# SS_SECE_V2_0.net
KiCad netlist of a schematic drawn in Altium Designer
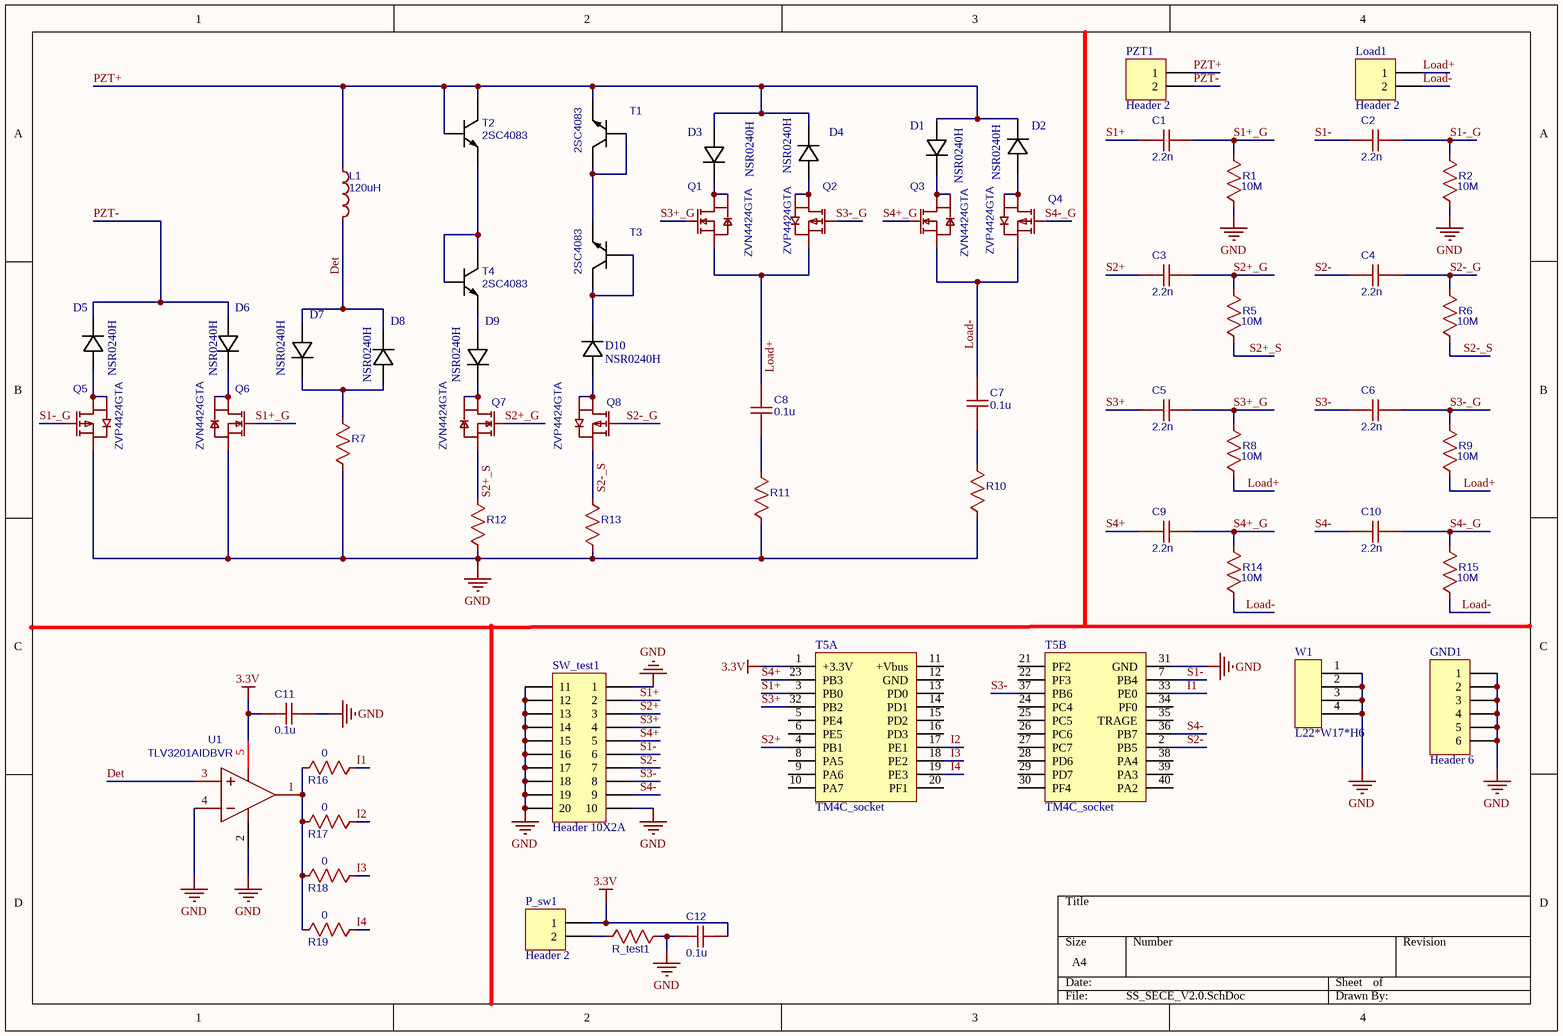
[diagram p0: SS_SECE_V2.0.SchDoc]

(export (version "E")
  (design (tool "Eeschema 10.0.6"))
  (components
    (comp (ref "C1")
      (value "2.2n")
      (footprint "C0603")
      (fields (field (name "CONTRIBUTOR") "LCEDA_Lib"))
      (libsource (lib "packet") (part "0.1u"))
    )
    (comp (ref "C2")
      (value "2.2n")
      (footprint "C0603")
      (fields (field (name "CONTRIBUTOR") "LCEDA_Lib"))
      (libsource (lib "packet") (part "0.1u"))
    )
    (comp (ref "C3")
      (value "2.2n")
      (footprint "C0603")
      (fields (field (name "CONTRIBUTOR") "LCEDA_Lib"))
      (libsource (lib "packet") (part "0.1u"))
    )
    (comp (ref "C4")
      (value "2.2n")
      (footprint "C0603")
      (fields (field (name "CONTRIBUTOR") "LCEDA_Lib"))
      (libsource (lib "packet") (part "0.1u"))
    )
    (comp (ref "C5")
      (value "2.2n")
      (footprint "C0603")
      (fields (field (name "CONTRIBUTOR") "LCEDA_Lib"))
      (libsource (lib "packet") (part "0.1u"))
    )
    (comp (ref "C6")
      (value "2.2n")
      (footprint "C0603")
      (fields (field (name "CONTRIBUTOR") "LCEDA_Lib"))
      (libsource (lib "packet") (part "0.1u"))
    )
    (comp (ref "C7")
      (value "0.1u")
      (footprint "Cap2220")
      (fields (field (name "CONTRIBUTOR") "LCEDA_Lib"))
      (libsource (lib "packet") (part "0.1u"))
    )
    (comp (ref "C8")
      (value "0.1u")
      (footprint "Cap2220")
      (fields (field (name "CONTRIBUTOR") "LCEDA_Lib"))
      (libsource (lib "packet") (part "0.1u"))
    )
    (comp (ref "C9")
      (value "2.2n")
      (footprint "C0603")
      (fields (field (name "CONTRIBUTOR") "LCEDA_Lib"))
      (libsource (lib "packet") (part "0.1u"))
    )
    (comp (ref "C10")
      (value "2.2n")
      (footprint "C0603")
      (fields (field (name "CONTRIBUTOR") "LCEDA_Lib"))
      (libsource (lib "packet") (part "0.1u"))
    )
    (comp (ref "C11")
      (value "0.1u")
      (footprint "C0603")
      (fields (field (name "CONTRIBUTOR") "LCEDA_Lib"))
      (libsource (lib "packet") (part "0.1u"))
    )
    (comp (ref "C12")
      (value "0.1u")
      (footprint "C0603")
      (fields (field (name "CONTRIBUTOR") "LCEDA_Lib"))
      (libsource (lib "packet") (part "0.1u"))
    )
    (comp (ref "D1") (value "NSR0240H") (footprint "SOD-323") (libsource (lib "packet") (part "NSR0240H")))
    (comp (ref "D2") (value "NSR0240H") (footprint "SOD-323") (libsource (lib "packet") (part "NSR0240H")))
    (comp (ref "D3") (value "NSR0240H") (footprint "SOD-323") (libsource (lib "packet") (part "NSR0240H")))
    (comp (ref "D4") (value "NSR0240H") (footprint "SOD-323") (libsource (lib "packet") (part "NSR0240H")))
    (comp (ref "D5") (value "NSR0240H") (footprint "SOD-323") (libsource (lib "packet") (part "NSR0240H")))
    (comp (ref "D6") (value "NSR0240H") (footprint "SOD-323") (libsource (lib "packet") (part "NSR0240H")))
    (comp (ref "D7") (value "NSR0240H") (footprint "SOD-323") (libsource (lib "packet") (part "NSR0240H")))
    (comp (ref "D8") (value "NSR0240H") (footprint "SOD-323") (libsource (lib "packet") (part "NSR0240H")))
    (comp (ref "D9") (value "NSR0240H") (footprint "SOD-323") (libsource (lib "packet") (part "NSR0240H")))
    (comp (ref "D10") (value "NSR0240H") (footprint "SOD-323") (libsource (lib "packet") (part "NSR0240H")))
    (comp (ref "GND1")
      (value "Header 6")
      (footprint "HDR1X6")
      (description "Header, 6-Pin")
      (fields (field (name "PUBLISHER") "Altium Limited"))
      (libsource (lib "Miscellaneous Connectors") (part "Header 6"))
    )
    (comp (ref "L1")
      (value "120uH")
      (footprint "120uH")
      (fields
        (field (name "BOM_MANUFACTURER PART") "VLU1012-470KB")
        (field (name "BOM_SUPPLIER PART") "C142466")
        (field (name "CONTRIBUTOR") "LCSC")
      )
      (libsource (lib "packet") (part "47uH"))
    )
    (comp (ref "Load1")
      (value "Header 2")
      (footprint "HDR1X2")
      (description "Header, 2-Pin")
      (fields (field (name "PUBLISHER") "Altium Limited"))
      (libsource (lib "Miscellaneous Connectors") (part "Header 2"))
    )
    (comp (ref "PZT1")
      (value "Header 2")
      (footprint "HDR1X2")
      (description "Header, 2-Pin")
      (fields (field (name "PUBLISHER") "Altium Limited"))
      (libsource (lib "Miscellaneous Connectors") (part "Header 2"))
    )
    (comp (ref "P_sw1")
      (value "Header 2")
      (footprint "HDR1X2")
      (description "Header, 2-Pin")
      (fields (field (name "PUBLISHER") "Altium Limited"))
      (libsource (lib "Miscellaneous Connectors") (part "Header 2"))
    )
    (comp (ref "Q1")
      (value "ZVN4424GTA")
      (footprint "SOT-223-4_L6.5-W3.5-P2.30-LS7.0-BR")
      (fields
        (field (name "BOM_SUPPLIER PART") "C397967")
        (field (name "BOM_MANUFACTURER PART") "ZVP4424GTA")
        (field (name "CONTRIBUTOR") "LCSC")
      )
      (libsource (lib "packet") (part "ZVN4424GTA"))
    )
    (comp (ref "Q2")
      (value "ZVP4424GTA")
      (footprint "SOT-223-4_L6.5-W3.5-P2.30-LS7.0-BR")
      (fields (field (name "BOM_SUPPLIER PART") "C397967") (field (name "CONTRIBUTOR") "LCSC"))
      (libsource (lib "packet") (part "ZVP4424GTA"))
    )
    (comp (ref "Q3")
      (value "ZVN4424GTA")
      (footprint "SOT-223-4_L6.5-W3.5-P2.30-LS7.0-BR")
      (fields
        (field (name "BOM_SUPPLIER PART") "C397967")
        (field (name "BOM_MANUFACTURER PART") "ZVP4424GTA")
        (field (name "CONTRIBUTOR") "LCSC")
      )
      (libsource (lib "packet") (part "ZVN4424GTA"))
    )
    (comp (ref "Q4")
      (value "ZVP4424GTA")
      (footprint "SOT-223-4_L6.5-W3.5-P2.30-LS7.0-BR")
      (fields (field (name "BOM_SUPPLIER PART") "C397967") (field (name "CONTRIBUTOR") "LCSC"))
      (libsource (lib "packet") (part "ZVP4424GTA"))
    )
    (comp (ref "Q5")
      (value "ZVP4424GTA")
      (footprint "SOT-223-4_L6.5-W3.5-P2.30-LS7.0-BR")
      (fields (field (name "BOM_SUPPLIER PART") "C397967") (field (name "CONTRIBUTOR") "LCSC"))
      (libsource (lib "packet") (part "ZVP4424GTA"))
    )
    (comp (ref "Q6")
      (value "ZVN4424GTA")
      (footprint "SOT-223-4_L6.5-W3.5-P2.30-LS7.0-BR")
      (fields
        (field (name "BOM_SUPPLIER PART") "C397967")
        (field (name "BOM_MANUFACTURER PART") "ZVP4424GTA")
        (field (name "CONTRIBUTOR") "LCSC")
      )
      (libsource (lib "packet") (part "ZVN4424GTA"))
    )
    (comp (ref "Q7")
      (value "ZVN4424GTA")
      (footprint "SOT-223-4_L6.5-W3.5-P2.30-LS7.0-BR")
      (fields
        (field (name "BOM_SUPPLIER PART") "C397967")
        (field (name "BOM_MANUFACTURER PART") "ZVP4424GTA")
        (field (name "CONTRIBUTOR") "LCSC")
      )
      (libsource (lib "packet") (part "ZVN4424GTA"))
    )
    (comp (ref "Q8")
      (value "ZVP4424GTA")
      (footprint "SOT-223-4_L6.5-W3.5-P2.30-LS7.0-BR")
      (fields (field (name "BOM_SUPPLIER PART") "C397967") (field (name "CONTRIBUTOR") "LCSC"))
      (libsource (lib "packet") (part "ZVP4424GTA"))
    )
    (comp (ref "R1")
      (value "10M")
      (footprint "R0603")
      (fields (field (name "CONTRIBUTOR") "LCEDA_Lib"))
      (libsource (lib "packet") (part "1k"))
    )
    (comp (ref "R2")
      (value "10M")
      (footprint "R0603")
      (fields (field (name "CONTRIBUTOR") "LCEDA_Lib"))
      (libsource (lib "packet") (part "1k"))
    )
    (comp (ref "R5")
      (value "10M")
      (footprint "R0603")
      (fields (field (name "CONTRIBUTOR") "LCEDA_Lib"))
      (libsource (lib "packet") (part "1k"))
    )
    (comp (ref "R6")
      (value "10M")
      (footprint "R0603")
      (fields (field (name "CONTRIBUTOR") "LCEDA_Lib"))
      (libsource (lib "packet") (part "1k"))
    )
    (comp (ref "R7")
      (value "0")
      (footprint "R0603")
      (fields (field (name "CONTRIBUTOR") "LCEDA_Lib"))
      (libsource (lib "packet") (part "1k"))
    )
    (comp (ref "R8")
      (value "10M")
      (footprint "R0603")
      (fields (field (name "CONTRIBUTOR") "LCEDA_Lib"))
      (libsource (lib "packet") (part "1k"))
    )
    (comp (ref "R9")
      (value "10M")
      (footprint "R0603")
      (fields (field (name "CONTRIBUTOR") "LCEDA_Lib"))
      (libsource (lib "packet") (part "1k"))
    )
    (comp (ref "R10")
      (value "0")
      (footprint "R0603")
      (fields (field (name "CONTRIBUTOR") "LCEDA_Lib"))
      (libsource (lib "packet") (part "1k"))
    )
    (comp (ref "R11")
      (value "0")
      (footprint "R0603")
      (fields (field (name "CONTRIBUTOR") "LCEDA_Lib"))
      (libsource (lib "packet") (part "1k"))
    )
    (comp (ref "R12")
      (value "0")
      (footprint "R0603")
      (fields (field (name "CONTRIBUTOR") "LCEDA_Lib"))
      (libsource (lib "packet") (part "1k"))
    )
    (comp (ref "R13")
      (value "0")
      (footprint "R0603")
      (fields (field (name "CONTRIBUTOR") "LCEDA_Lib"))
      (libsource (lib "packet") (part "1k"))
    )
    (comp (ref "R14")
      (value "10M")
      (footprint "R0603")
      (fields (field (name "CONTRIBUTOR") "LCEDA_Lib"))
      (libsource (lib "packet") (part "1k"))
    )
    (comp (ref "R15")
      (value "10M")
      (footprint "R0603")
      (fields (field (name "CONTRIBUTOR") "LCEDA_Lib"))
      (libsource (lib "packet") (part "1k"))
    )
    (comp (ref "R16")
      (value "0")
      (footprint "R0603")
      (fields (field (name "CONTRIBUTOR") "LCEDA_Lib"))
      (libsource (lib "packet") (part "1k"))
    )
    (comp (ref "R17")
      (value "0")
      (footprint "R0603")
      (fields (field (name "CONTRIBUTOR") "LCEDA_Lib"))
      (libsource (lib "packet") (part "1k"))
    )
    (comp (ref "R18")
      (value "0")
      (footprint "R0603")
      (fields (field (name "CONTRIBUTOR") "LCEDA_Lib"))
      (libsource (lib "packet") (part "1k"))
    )
    (comp (ref "R19")
      (value "0")
      (footprint "R0603")
      (fields (field (name "CONTRIBUTOR") "LCEDA_Lib"))
      (libsource (lib "packet") (part "1k"))
    )
    (comp (ref "R_test1")
      (value "1k")
      (footprint "R0603")
      (fields (field (name "CONTRIBUTOR") "LCEDA_Lib"))
      (libsource (lib "packet") (part "1k"))
    )
    (comp (ref "SW_test1")
      (value "Header 10X2A")
      (footprint "HDR2X10_CEN")
      (description "Header, 10-Pin, Dual row")
      (fields (field (name "PUBLISHER") "Altium Limited"))
      (libsource (lib "Miscellaneous Connectors") (part "Header 10X2A"))
    )
    (comp (ref "T1") (value "2SC4083") (footprint "SOT 323") (libsource (lib "packet") (part "2SC4083")))
    (comp (ref "T2") (value "2SC4083") (footprint "SOT 323") (libsource (lib "packet") (part "2SC4083")))
    (comp (ref "T3") (value "2SC4083") (footprint "SOT 323") (libsource (lib "packet") (part "2SC4083")))
    (comp (ref "T4") (value "2SC4083") (footprint "SOT 323") (libsource (lib "packet") (part "2SC4083")))
    (comp (ref "T5")
      (value "TM4C_socket")
      (footprint "Tm4c_socket")
      (libsource (lib "") (part "Tm4c_socket_1"))
    )
    (comp (ref "U1")
      (value "TLV3201AIDBVR")
      (footprint "SOT-23-5_L3.0-W1.7-P0.95-LS2.8-BR")
      (fields (field (name "BOM_SUPPLIER PART") "C105188"))
      (libsource (lib "packet") (part "TLV3201AIDBVR"))
    )
    (comp (ref "W1")
      (value "L22*W17*H6")
      (footprint "L22*W17*H6")
      (libsource (lib "packet") (part "L22*W17*H6"))
    )
  )
  (nets
    (net (code "1") (name "/Det") (class "Default")
      (node (ref "D7") (pin "2") (pinfunction "A_2") (pintype "passive"))
      (node (ref "D8") (pin "1") (pinfunction "C_1") (pintype "passive"))
      (node (ref "L1") (pin "2") (pinfunction "2_2") (pintype "passive"))
      (node (ref "U1") (pin "3") (pinfunction "IN+_3") (pintype "passive"))
    )
    (net (code "2") (name "/I1") (class "Default")
      (node (ref "R16") (pin "2") (pinfunction "2_2") (pintype "passive"))
      (node (ref "T5") (pin "33") (pinfunction "PE0_33") (pintype "passive"))
    )
    (net (code "3") (name "/I2") (class "Default")
      (node (ref "R17") (pin "2") (pinfunction "2_2") (pintype "passive"))
      (node (ref "T5") (pin "17") (pinfunction "PE1_17") (pintype "passive"))
    )
    (net (code "4") (name "/I3") (class "Default")
      (node (ref "R18") (pin "2") (pinfunction "2_2") (pintype "passive"))
      (node (ref "T5") (pin "18") (pinfunction "PE2_18") (pintype "passive"))
    )
    (net (code "5") (name "/I4") (class "Default")
      (node (ref "R19") (pin "2") (pinfunction "2_2") (pintype "passive"))
      (node (ref "T5") (pin "19") (pinfunction "PE3_19") (pintype "passive"))
    )
    (net (code "6") (name "/Load+") (class "Default")
      (node (ref "C8") (pin "2") (pinfunction "2_2") (pintype "passive"))
      (node (ref "Load1") (pin "1") (pinfunction "1_1") (pintype "passive"))
      (node (ref "Q1") (pin "3") (pinfunction "S_3") (pintype "passive"))
      (node (ref "Q2") (pin "3") (pinfunction "S_3") (pintype "passive"))
      (node (ref "R8") (pin "1") (pinfunction "1_1") (pintype "passive"))
      (node (ref "R9") (pin "1") (pinfunction "1_1") (pintype "passive"))
    )
    (net (code "7") (name "/Load-") (class "Default")
      (node (ref "C7") (pin "2") (pinfunction "2_2") (pintype "passive"))
      (node (ref "Load1") (pin "2") (pinfunction "2_2") (pintype "passive"))
      (node (ref "Q3") (pin "3") (pinfunction "S_3") (pintype "passive"))
      (node (ref "Q4") (pin "3") (pinfunction "S_3") (pintype "passive"))
      (node (ref "R14") (pin "1") (pinfunction "1_1") (pintype "passive"))
      (node (ref "R15") (pin "1") (pinfunction "1_1") (pintype "passive"))
    )
    (net (code "8") (name "/PZT+") (class "Default")
      (node (ref "D1") (pin "2") (pinfunction "A_2") (pintype "passive"))
      (node (ref "D2") (pin "1") (pinfunction "C_1") (pintype "passive"))
      (node (ref "D3") (pin "2") (pinfunction "A_2") (pintype "passive"))
      (node (ref "D4") (pin "1") (pinfunction "C_1") (pintype "passive"))
      (node (ref "L1") (pin "1") (pinfunction "1_1") (pintype "passive"))
      (node (ref "PZT1") (pin "1") (pinfunction "1_1") (pintype "passive"))
      (node (ref "T1") (pin "1") (pinfunction "E_1") (pintype "passive"))
      (node (ref "T2") (pin "2") (pinfunction "B_2") (pintype "passive"))
      (node (ref "T2") (pin "3") (pinfunction "C_3") (pintype "passive"))
    )
    (net (code "9") (name "/PZT-") (class "Default")
      (node (ref "D5") (pin "1") (pinfunction "C_1") (pintype "passive"))
      (node (ref "D6") (pin "2") (pinfunction "A_2") (pintype "passive"))
      (node (ref "PZT1") (pin "2") (pinfunction "2_2") (pintype "passive"))
    )
    (net (code "10") (name "/S1+") (class "Default")
      (node (ref "C1") (pin "1") (pinfunction "1_1") (pintype "passive"))
      (node (ref "SW_test1") (pin "2") (pinfunction "2_2") (pintype "passive"))
      (node (ref "T5") (pin "3") (pinfunction "PB0_3") (pintype "passive"))
    )
    (net (code "11") (name "/S1+_G") (class "Default")
      (node (ref "C1") (pin "2") (pinfunction "2_2") (pintype "passive"))
      (node (ref "Q6") (pin "1") (pinfunction "G_1") (pintype "passive"))
      (node (ref "R1") (pin "2") (pinfunction "2_2") (pintype "passive"))
    )
    (net (code "12") (name "/S1-") (class "Default")
      (node (ref "C2") (pin "1") (pinfunction "1_1") (pintype "passive"))
      (node (ref "SW_test1") (pin "6") (pinfunction "6_6") (pintype "passive"))
      (node (ref "T5") (pin "7") (pinfunction "PB4_7") (pintype "passive"))
    )
    (net (code "13") (name "/S1-_G") (class "Default")
      (node (ref "C2") (pin "2") (pinfunction "2_2") (pintype "passive"))
      (node (ref "Q5") (pin "1") (pinfunction "G_1") (pintype "passive"))
      (node (ref "R2") (pin "2") (pinfunction "2_2") (pintype "passive"))
    )
    (net (code "14") (name "/S2+") (class "Default")
      (node (ref "C3") (pin "1") (pinfunction "1_1") (pintype "passive"))
      (node (ref "SW_test1") (pin "3") (pinfunction "3_3") (pintype "passive"))
      (node (ref "T5") (pin "4") (pinfunction "PB1_4") (pintype "passive"))
    )
    (net (code "15") (name "/S2+_G") (class "Default")
      (node (ref "C3") (pin "2") (pinfunction "2_2") (pintype "passive"))
      (node (ref "Q7") (pin "1") (pinfunction "G_1") (pintype "passive"))
      (node (ref "R5") (pin "2") (pinfunction "2_2") (pintype "passive"))
    )
    (net (code "16") (name "/S2+_S") (class "Default")
      (node (ref "Q7") (pin "3") (pinfunction "S_3") (pintype "passive"))
      (node (ref "R12") (pin "2") (pinfunction "2_2") (pintype "passive"))
      (node (ref "R5") (pin "1") (pinfunction "1_1") (pintype "passive"))
    )
    (net (code "17") (name "/S2-") (class "Default")
      (node (ref "C4") (pin "1") (pinfunction "1_1") (pintype "passive"))
      (node (ref "SW_test1") (pin "7") (pinfunction "7_7") (pintype "passive"))
      (node (ref "T5") (pin "2") (pinfunction "PB5_2") (pintype "passive"))
    )
    (net (code "18") (name "/S2-_G") (class "Default")
      (node (ref "C4") (pin "2") (pinfunction "2_2") (pintype "passive"))
      (node (ref "Q8") (pin "1") (pinfunction "G_1") (pintype "passive"))
      (node (ref "R6") (pin "2") (pinfunction "2_2") (pintype "passive"))
    )
    (net (code "19") (name "/S2-_S") (class "Default")
      (node (ref "Q8") (pin "3") (pinfunction "S_3") (pintype "passive"))
      (node (ref "R13") (pin "2") (pinfunction "2_2") (pintype "passive"))
      (node (ref "R6") (pin "1") (pinfunction "1_1") (pintype "passive"))
    )
    (net (code "20") (name "/S3+") (class "Default")
      (node (ref "C5") (pin "1") (pinfunction "1_1") (pintype "passive"))
      (node (ref "SW_test1") (pin "4") (pinfunction "4_4") (pintype "passive"))
      (node (ref "T5") (pin "32") (pinfunction "PB2_32") (pintype "passive"))
    )
    (net (code "21") (name "/S3+_G") (class "Default")
      (node (ref "C5") (pin "2") (pinfunction "2_2") (pintype "passive"))
      (node (ref "Q1") (pin "1") (pinfunction "G_1") (pintype "passive"))
      (node (ref "R8") (pin "2") (pinfunction "2_2") (pintype "passive"))
    )
    (net (code "22") (name "/S3-") (class "Default")
      (node (ref "C6") (pin "1") (pinfunction "1_1") (pintype "passive"))
      (node (ref "SW_test1") (pin "8") (pinfunction "8_8") (pintype "passive"))
      (node (ref "T5") (pin "37") (pinfunction "PB6_37") (pintype "passive"))
    )
    (net (code "23") (name "/S3-_G") (class "Default")
      (node (ref "C6") (pin "2") (pinfunction "2_2") (pintype "passive"))
      (node (ref "Q2") (pin "1") (pinfunction "G_1") (pintype "passive"))
      (node (ref "R9") (pin "2") (pinfunction "2_2") (pintype "passive"))
    )
    (net (code "24") (name "/S4+") (class "Default")
      (node (ref "C9") (pin "1") (pinfunction "1_1") (pintype "passive"))
      (node (ref "SW_test1") (pin "5") (pinfunction "5_5") (pintype "passive"))
      (node (ref "T5") (pin "23") (pinfunction "PB3_23") (pintype "passive"))
    )
    (net (code "25") (name "/S4+_G") (class "Default")
      (node (ref "C9") (pin "2") (pinfunction "2_2") (pintype "passive"))
      (node (ref "Q3") (pin "1") (pinfunction "G_1") (pintype "passive"))
      (node (ref "R14") (pin "2") (pinfunction "2_2") (pintype "passive"))
    )
    (net (code "26") (name "/S4-") (class "Default")
      (node (ref "C10") (pin "1") (pinfunction "1_1") (pintype "passive"))
      (node (ref "SW_test1") (pin "9") (pinfunction "9_9") (pintype "passive"))
      (node (ref "T5") (pin "36") (pinfunction "PB7_36") (pintype "passive"))
    )
    (net (code "27") (name "/S4-_G") (class "Default")
      (node (ref "C10") (pin "2") (pinfunction "2_2") (pintype "passive"))
      (node (ref "Q4") (pin "1") (pinfunction "G_1") (pintype "passive"))
      (node (ref "R15") (pin "2") (pinfunction "2_2") (pintype "passive"))
    )
    (net (code "28") (name "3.3V") (class "Default")
      (node (ref "C11") (pin "1") (pinfunction "1_1") (pintype "passive"))
      (node (ref "C12") (pin "1") (pinfunction "1_1") (pintype "passive"))
      (node (ref "P_sw1") (pin "1") (pinfunction "1_1") (pintype "passive"))
      (node (ref "T5") (pin "1") (pinfunction "+3.3V_1") (pintype "passive"))
      (node (ref "U1") (pin "5") (pinfunction "VCC_5") (pintype "passive"))
    )
    (net (code "29") (name "GND") (class "Default")
      (node (ref "C11") (pin "2") (pinfunction "2_2") (pintype "passive"))
      (node (ref "C12") (pin "2") (pinfunction "2_2") (pintype "passive"))
      (node (ref "GND1") (pin "1") (pinfunction "1_1") (pintype "passive"))
      (node (ref "GND1") (pin "2") (pinfunction "2_2") (pintype "passive"))
      (node (ref "GND1") (pin "3") (pinfunction "3_3") (pintype "passive"))
      (node (ref "GND1") (pin "4") (pinfunction "4_4") (pintype "passive"))
      (node (ref "GND1") (pin "5") (pinfunction "5_5") (pintype "passive"))
      (node (ref "GND1") (pin "6") (pinfunction "6_6") (pintype "passive"))
      (node (ref "Q5") (pin "3") (pinfunction "S_3") (pintype "passive"))
      (node (ref "Q6") (pin "3") (pinfunction "S_3") (pintype "passive"))
      (node (ref "R1") (pin "1") (pinfunction "1_1") (pintype "passive"))
      (node (ref "R10") (pin "1") (pinfunction "1_1") (pintype "passive"))
      (node (ref "R11") (pin "1") (pinfunction "1_1") (pintype "passive"))
      (node (ref "R12") (pin "1") (pinfunction "1_1") (pintype "passive"))
      (node (ref "R13") (pin "1") (pinfunction "1_1") (pintype "passive"))
      (node (ref "R2") (pin "1") (pinfunction "1_1") (pintype "passive"))
      (node (ref "R7") (pin "1") (pinfunction "1_1") (pintype "passive"))
      (node (ref "R_test1") (pin "2") (pinfunction "2_2") (pintype "passive"))
      (node (ref "SW_test1") (pin "1") (pinfunction "1_1") (pintype "passive"))
      (node (ref "SW_test1") (pin "10") (pinfunction "10_10") (pintype "passive"))
      (node (ref "SW_test1") (pin "11") (pinfunction "11_11") (pintype "passive"))
      (node (ref "SW_test1") (pin "12") (pinfunction "12_12") (pintype "passive"))
      (node (ref "SW_test1") (pin "13") (pinfunction "13_13") (pintype "passive"))
      (node (ref "SW_test1") (pin "14") (pinfunction "14_14") (pintype "passive"))
      (node (ref "SW_test1") (pin "15") (pinfunction "15_15") (pintype "passive"))
      (node (ref "SW_test1") (pin "16") (pinfunction "16_16") (pintype "passive"))
      (node (ref "SW_test1") (pin "17") (pinfunction "17_17") (pintype "passive"))
      (node (ref "SW_test1") (pin "18") (pinfunction "18_18") (pintype "passive"))
      (node (ref "SW_test1") (pin "19") (pinfunction "19_19") (pintype "passive"))
      (node (ref "SW_test1") (pin "20") (pinfunction "20_20") (pintype "passive"))
      (node (ref "T5") (pin "31") (pinfunction "GND_31") (pintype "passive"))
      (node (ref "U1") (pin "2") (pinfunction "GND_2") (pintype "passive"))
      (node (ref "U1") (pin "4") (pinfunction "IN-_4") (pintype "passive"))
      (node (ref "W1") (pin "1") (pinfunction "GND_1") (pintype "passive"))
      (node (ref "W1") (pin "2") (pinfunction "2_2") (pintype "passive"))
      (node (ref "W1") (pin "3") (pinfunction "3_3") (pintype "passive"))
      (node (ref "W1") (pin "4") (pinfunction "4_4") (pintype "passive"))
    )
    (net (code "30") (name "Net-(C7-Pad1)") (class "Default")
      (node (ref "C7") (pin "1") (pinfunction "1_1") (pintype "passive"))
      (node (ref "R10") (pin "2") (pinfunction "2_2") (pintype "passive"))
    )
    (net (code "31") (name "Net-(C8-Pad1)") (class "Default")
      (node (ref "C8") (pin "1") (pinfunction "1_1") (pintype "passive"))
      (node (ref "R11") (pin "2") (pinfunction "2_2") (pintype "passive"))
    )
    (net (code "32") (name "Net-(D1-C)") (class "Default")
      (node (ref "D1") (pin "1") (pinfunction "C_1") (pintype "passive"))
      (node (ref "Q3") (pin "2") (pinfunction "D_2") (pintype "passive"))
      (node (ref "Q3") (pin "4") (pinfunction "D_4") (pintype "passive"))
    )
    (net (code "33") (name "Net-(D2-A)") (class "Default")
      (node (ref "D2") (pin "2") (pinfunction "A_2") (pintype "passive"))
      (node (ref "Q4") (pin "2") (pinfunction "D_2") (pintype "passive"))
      (node (ref "Q4") (pin "4") (pinfunction "D_4") (pintype "passive"))
    )
    (net (code "34") (name "Net-(D3-C)") (class "Default")
      (node (ref "D3") (pin "1") (pinfunction "C_1") (pintype "passive"))
      (node (ref "Q1") (pin "2") (pinfunction "D_2") (pintype "passive"))
      (node (ref "Q1") (pin "4") (pinfunction "D_4") (pintype "passive"))
    )
    (net (code "35") (name "Net-(D4-A)") (class "Default")
      (node (ref "D4") (pin "2") (pinfunction "A_2") (pintype "passive"))
      (node (ref "Q2") (pin "2") (pinfunction "D_2") (pintype "passive"))
      (node (ref "Q2") (pin "4") (pinfunction "D_4") (pintype "passive"))
    )
    (net (code "36") (name "Net-(D5-A)") (class "Default")
      (node (ref "D5") (pin "2") (pinfunction "A_2") (pintype "passive"))
      (node (ref "Q5") (pin "2") (pinfunction "D_2") (pintype "passive"))
      (node (ref "Q5") (pin "4") (pinfunction "D_4") (pintype "passive"))
    )
    (net (code "37") (name "Net-(D6-C)") (class "Default")
      (node (ref "D6") (pin "1") (pinfunction "C_1") (pintype "passive"))
      (node (ref "Q6") (pin "2") (pinfunction "D_2") (pintype "passive"))
      (node (ref "Q6") (pin "4") (pinfunction "D_4") (pintype "passive"))
    )
    (net (code "38") (name "Net-(D7-C)") (class "Default")
      (node (ref "D7") (pin "1") (pinfunction "C_1") (pintype "passive"))
      (node (ref "D8") (pin "2") (pinfunction "A_2") (pintype "passive"))
      (node (ref "R7") (pin "2") (pinfunction "2_2") (pintype "passive"))
    )
    (net (code "39") (name "Net-(D9-A)") (class "Default")
      (node (ref "D9") (pin "2") (pinfunction "A_2") (pintype "passive"))
      (node (ref "T4") (pin "1") (pinfunction "E_1") (pintype "passive"))
    )
    (net (code "40") (name "Net-(D9-C)") (class "Default")
      (node (ref "D9") (pin "1") (pinfunction "C_1") (pintype "passive"))
      (node (ref "Q7") (pin "2") (pinfunction "D_2") (pintype "passive"))
      (node (ref "Q7") (pin "4") (pinfunction "D_4") (pintype "passive"))
    )
    (net (code "41") (name "Net-(D10-A)") (class "Default")
      (node (ref "D10") (pin "2") (pinfunction "A_2") (pintype "passive"))
      (node (ref "Q8") (pin "2") (pinfunction "D_2") (pintype "passive"))
      (node (ref "Q8") (pin "4") (pinfunction "D_4") (pintype "passive"))
    )
    (net (code "42") (name "Net-(D10-C)") (class "Default")
      (node (ref "D10") (pin "1") (pinfunction "C_1") (pintype "passive"))
      (node (ref "T3") (pin "2") (pinfunction "B_2") (pintype "passive"))
      (node (ref "T3") (pin "3") (pinfunction "C_3") (pintype "passive"))
    )
    (net (code "43") (name "Net-(P_sw1-Pad2)") (class "Default")
      (node (ref "P_sw1") (pin "2") (pinfunction "2_2") (pintype "passive"))
      (node (ref "R_test1") (pin "1") (pinfunction "1_1") (pintype "passive"))
    )
    (net (code "44") (name "Net-(T1-B)") (class "Default")
      (node (ref "T1") (pin "2") (pinfunction "B_2") (pintype "passive"))
      (node (ref "T1") (pin "3") (pinfunction "C_3") (pintype "passive"))
      (node (ref "T3") (pin "1") (pinfunction "E_1") (pintype "passive"))
    )
    (net (code "45") (name "Net-(T2-E)") (class "Default")
      (node (ref "T2") (pin "1") (pinfunction "E_1") (pintype "passive"))
      (node (ref "T4") (pin "2") (pinfunction "B_2") (pintype "passive"))
      (node (ref "T4") (pin "3") (pinfunction "C_3") (pintype "passive"))
    )
    (net (code "46") (name "Net-(U1-OUT)") (class "Default")
      (node (ref "R16") (pin "1") (pinfunction "1_1") (pintype "passive"))
      (node (ref "R17") (pin "1") (pinfunction "1_1") (pintype "passive"))
      (node (ref "R18") (pin "1") (pinfunction "1_1") (pintype "passive"))
      (node (ref "R19") (pin "1") (pinfunction "1_1") (pintype "passive"))
      (node (ref "U1") (pin "1") (pinfunction "OUT_1") (pintype "passive"))
    )
    (net (code "47") (name "unconnected-(T5A-+Vbus-Pad11)") (class "Default")
      (node (ref "T5") (pin "11") (pinfunction "+Vbus_11") (pintype "passive"))
    )
    (net (code "48") (name "unconnected-(T5A-GND-Pad12)") (class "Default")
      (node (ref "T5") (pin "12") (pinfunction "GND_12") (pintype "passive"))
    )
    (net (code "49") (name "unconnected-(T5A-PA5-Pad8)") (class "Default")
      (node (ref "T5") (pin "8") (pinfunction "PA5_8") (pintype "passive"))
    )
    (net (code "50") (name "unconnected-(T5A-PA6-Pad9)") (class "Default")
      (node (ref "T5") (pin "9") (pinfunction "PA6_9") (pintype "passive"))
    )
    (net (code "51") (name "unconnected-(T5A-PA7-Pad10)") (class "Default")
      (node (ref "T5") (pin "10") (pinfunction "PA7_10") (pintype "passive"))
    )
    (net (code "52") (name "unconnected-(T5A-PD0-Pad13)") (class "Default")
      (node (ref "T5") (pin "13") (pinfunction "PD0_13") (pintype "passive"))
    )
    (net (code "53") (name "unconnected-(T5A-PD1-Pad14)") (class "Default")
      (node (ref "T5") (pin "14") (pinfunction "PD1_14") (pintype "passive"))
    )
    (net (code "54") (name "unconnected-(T5A-PD2-Pad15)") (class "Default")
      (node (ref "T5") (pin "15") (pinfunction "PD2_15") (pintype "passive"))
    )
    (net (code "55") (name "unconnected-(T5A-PD3-Pad16)") (class "Default")
      (node (ref "T5") (pin "16") (pinfunction "PD3_16") (pintype "passive"))
    )
    (net (code "56") (name "unconnected-(T5A-PE4-Pad5)") (class "Default")
      (node (ref "T5") (pin "5") (pinfunction "PE4_5") (pintype "passive"))
    )
    (net (code "57") (name "unconnected-(T5A-PE5-Pad6)") (class "Default")
      (node (ref "T5") (pin "6") (pinfunction "PE5_6") (pintype "passive"))
    )
    (net (code "58") (name "unconnected-(T5A-PF1-Pad20)") (class "Default")
      (node (ref "T5") (pin "20") (pinfunction "PF1_20") (pintype "passive"))
    )
    (net (code "59") (name "unconnected-(T5B-PA2-Pad40)") (class "Default")
      (node (ref "T5") (pin "40") (pinfunction "PA2_40") (pintype "passive"))
    )
    (net (code "60") (name "unconnected-(T5B-PA3-Pad39)") (class "Default")
      (node (ref "T5") (pin "39") (pinfunction "PA3_39") (pintype "passive"))
    )
    (net (code "61") (name "unconnected-(T5B-PA4-Pad38)") (class "Default")
      (node (ref "T5") (pin "38") (pinfunction "PA4_38") (pintype "passive"))
    )
    (net (code "62") (name "unconnected-(T5B-PC4-Pad24)") (class "Default")
      (node (ref "T5") (pin "24") (pinfunction "PC4_24") (pintype "passive"))
    )
    (net (code "63") (name "unconnected-(T5B-PC5-Pad25)") (class "Default")
      (node (ref "T5") (pin "25") (pinfunction "PC5_25") (pintype "passive"))
    )
    (net (code "64") (name "unconnected-(T5B-PC6-Pad26)") (class "Default")
      (node (ref "T5") (pin "26") (pinfunction "PC6_26") (pintype "passive"))
    )
    (net (code "65") (name "unconnected-(T5B-PC7-Pad27)") (class "Default")
      (node (ref "T5") (pin "27") (pinfunction "PC7_27") (pintype "passive"))
    )
    (net (code "66") (name "unconnected-(T5B-PD6-Pad28)") (class "Default")
      (node (ref "T5") (pin "28") (pinfunction "PD6_28") (pintype "passive"))
    )
    (net (code "67") (name "unconnected-(T5B-PD7-Pad29)") (class "Default")
      (node (ref "T5") (pin "29") (pinfunction "PD7_29") (pintype "passive"))
    )
    (net (code "68") (name "unconnected-(T5B-PF0-Pad34)") (class "Default")
      (node (ref "T5") (pin "34") (pinfunction "PF0_34") (pintype "passive"))
    )
    (net (code "69") (name "unconnected-(T5B-PF2-Pad21)") (class "Default")
      (node (ref "T5") (pin "21") (pinfunction "PF2_21") (pintype "passive"))
    )
    (net (code "70") (name "unconnected-(T5B-PF3-Pad22)") (class "Default")
      (node (ref "T5") (pin "22") (pinfunction "PF3_22") (pintype "passive"))
    )
    (net (code "71") (name "unconnected-(T5B-PF4-Pad30)") (class "Default")
      (node (ref "T5") (pin "30") (pinfunction "PF4_30") (pintype "passive"))
    )
    (net (code "72") (name "unconnected-(T5B-TRAGE-Pad35)") (class "Default")
      (node (ref "T5") (pin "35") (pinfunction "TRAGE_35") (pintype "passive"))
    )
  )
)
